# internet_enabled_rov.net
KiCad netlist of a schematic drawn in EAGLE
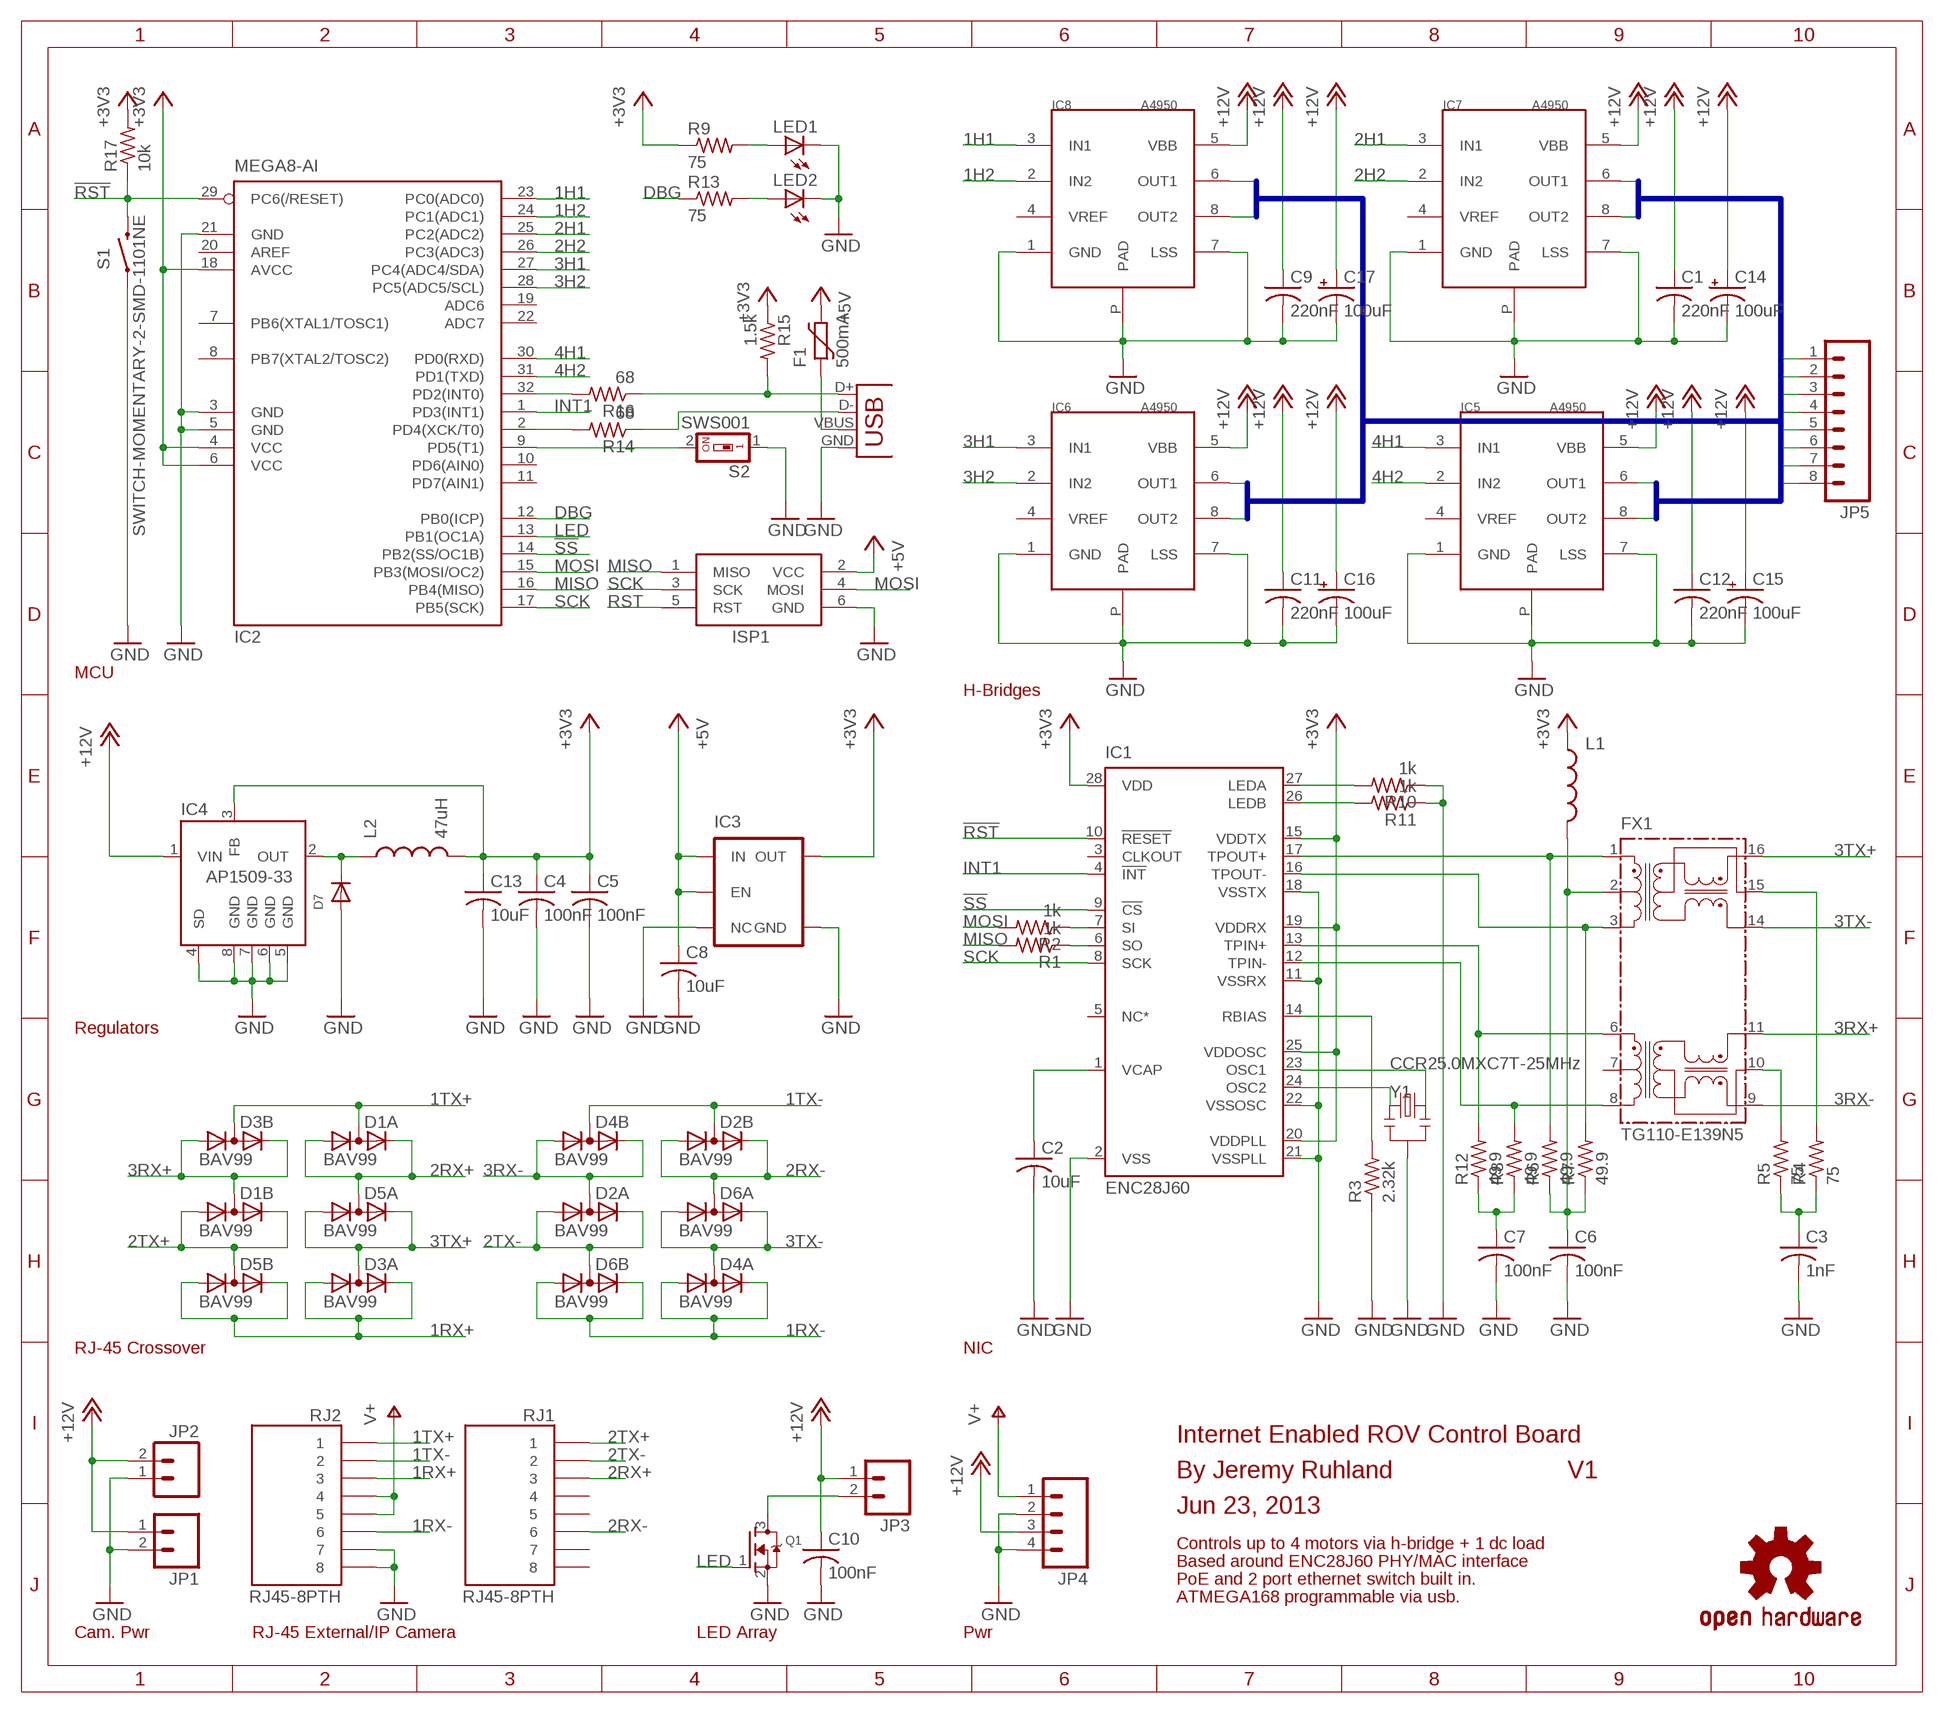
[diagram p0: schematic, sheet 1]

(export (version "E")
  (design (tool "Eeschema 10.0.6"))
  (components
    (comp (ref "C1")
      (value "220nF")
      (footprint "eagle-import:C1206")
      (libsource (lib "eagle-import") (part "C-USC1206"))
    )
    (comp (ref "C2")
      (value "10uF")
      (footprint "eagle-import:C1206")
      (libsource (lib "eagle-import") (part "C-USC1206"))
    )
    (comp (ref "C3")
      (value "1nF")
      (footprint "eagle-import:C1206")
      (libsource (lib "eagle-import") (part "C-USC1206"))
    )
    (comp (ref "C4")
      (value "100nF")
      (footprint "eagle-import:C1206")
      (libsource (lib "eagle-import") (part "C-USC1206"))
    )
    (comp (ref "C5")
      (value "100nF")
      (footprint "eagle-import:C1206")
      (libsource (lib "eagle-import") (part "C-USC1206"))
    )
    (comp (ref "C6")
      (value "100nF")
      (footprint "eagle-import:C1206")
      (libsource (lib "eagle-import") (part "C-USC1206"))
    )
    (comp (ref "C7")
      (value "100nF")
      (footprint "eagle-import:C1206")
      (libsource (lib "eagle-import") (part "C-USC1206"))
    )
    (comp (ref "C8")
      (value "10uF")
      (footprint "eagle-import:C1206")
      (libsource (lib "eagle-import") (part "C-USC1206"))
    )
    (comp (ref "C9")
      (value "220nF")
      (footprint "eagle-import:C1206")
      (libsource (lib "eagle-import") (part "C-USC1206"))
    )
    (comp (ref "C10")
      (value "100nF")
      (footprint "eagle-import:C1206")
      (libsource (lib "eagle-import") (part "C-USC1206"))
    )
    (comp (ref "C11")
      (value "220nF")
      (footprint "eagle-import:C1206")
      (libsource (lib "eagle-import") (part "C-USC1206"))
    )
    (comp (ref "C12")
      (value "220nF")
      (footprint "eagle-import:C1206")
      (libsource (lib "eagle-import") (part "C-USC1206"))
    )
    (comp (ref "C13")
      (value "10uF")
      (footprint "eagle-import:C1206")
      (libsource (lib "eagle-import") (part "C-USC1206"))
    )
    (comp (ref "C14")
      (value "100uF")
      (footprint "eagle-import:PANASONIC_D")
      (libsource (lib "eagle-import") (part "CAP_POLD"))
    )
    (comp (ref "C15")
      (value "100uF")
      (footprint "eagle-import:PANASONIC_D")
      (libsource (lib "eagle-import") (part "CAP_POLD"))
    )
    (comp (ref "C16")
      (value "100uF")
      (footprint "eagle-import:PANASONIC_D")
      (libsource (lib "eagle-import") (part "CAP_POLD"))
    )
    (comp (ref "C17")
      (value "100uF")
      (footprint "eagle-import:PANASONIC_D")
      (libsource (lib "eagle-import") (part "CAP_POLD"))
    )
    (comp (ref "D1")
      (value "BAV99")
      (footprint "eagle-import:SOT363")
      (libsource (lib "eagle-import") (part "BAV99"))
    )
    (comp (ref "D2")
      (value "BAV99")
      (footprint "eagle-import:SOT363")
      (libsource (lib "eagle-import") (part "BAV99"))
    )
    (comp (ref "D3")
      (value "BAV99")
      (footprint "eagle-import:SOT363")
      (libsource (lib "eagle-import") (part "BAV99"))
    )
    (comp (ref "D4")
      (value "BAV99")
      (footprint "eagle-import:SOT363")
      (libsource (lib "eagle-import") (part "BAV99"))
    )
    (comp (ref "D5")
      (value "BAV99")
      (footprint "eagle-import:SOT363")
      (libsource (lib "eagle-import") (part "BAV99"))
    )
    (comp (ref "D6")
      (value "BAV99")
      (footprint "eagle-import:SOT363")
      (libsource (lib "eagle-import") (part "BAV99"))
    )
    (comp (ref "D7")
      (value "DIODESOD-123")
      (footprint "eagle-import:SOD-123")
      (libsource (lib "eagle-import") (part "DIODESOD-123"))
    )
    (comp (ref "F1")
      (value "500mA")
      (footprint "eagle-import:PTC0805")
      (libsource (lib "eagle-import") (part "FUSE_PTC-0805"))
    )
    (comp (ref "FX1")
      (value "TG110-E139N5")
      (footprint "eagle-import:N5")
      (libsource (lib "eagle-import") (part "TG110-EN5139"))
    )
    (comp (ref "IC1")
      (value "ENC28J60")
      (footprint "eagle-import:SO28W")
      (libsource (lib "eagle-import") (part "ENC28J60"))
    )
    (comp (ref "IC2")
      (value "MEGA8-AI")
      (footprint "eagle-import:TQFP32-08")
      (fields (field (name "MPN") "ATMEGA8-16AU"))
      (libsource (lib "eagle-import") (part "MEGA8-AI"))
    )
    (comp (ref "IC3")
      (value "V_REG_TPS76433SOT23-5")
      (footprint "eagle-import:SOT23-5")
      (libsource (lib "eagle-import") (part "V_REG_TPS76433SOT23-5"))
    )
    (comp (ref "IC4")
      (value "AP1509-33")
      (footprint "eagle-import:SOP-8")
      (libsource (lib "eagle-import") (part "AP1509"))
    )
    (comp (ref "IC5")
      (value "A4950")
      (footprint "eagle-import:SOIC-8-PAD")
      (libsource (lib "eagle-import") (part "A4950"))
    )
    (comp (ref "IC6")
      (value "A4950")
      (footprint "eagle-import:SOIC-8-PAD")
      (libsource (lib "eagle-import") (part "A4950"))
    )
    (comp (ref "IC7")
      (value "A4950")
      (footprint "eagle-import:SOIC-8-PAD")
      (libsource (lib "eagle-import") (part "A4950"))
    )
    (comp (ref "IC8")
      (value "A4950")
      (footprint "eagle-import:SOIC-8-PAD")
      (libsource (lib "eagle-import") (part "A4950"))
    )
    (comp (ref "ISP1")
      (value "AVRISP-6")
      (footprint "eagle-import:AVRISP")
      (libsource (lib "eagle-import") (part "AVRISP-6"))
    )
    (comp (ref "JP1")
      (value "M02LOCK")
      (footprint "eagle-import:1X02_LOCK")
      (libsource (lib "eagle-import") (part "M02LOCK"))
    )
    (comp (ref "JP2")
      (value "M02LOCK")
      (footprint "eagle-import:1X02_LOCK")
      (libsource (lib "eagle-import") (part "M02LOCK"))
    )
    (comp (ref "JP3")
      (value "M02LOCK")
      (footprint "eagle-import:1X02_LOCK")
      (libsource (lib "eagle-import") (part "M02LOCK"))
    )
    (comp (ref "JP4")
      (value "M04SCREW_LOCK")
      (footprint "eagle-import:SCREWTERMINAL-3.5MM-4_LOCK")
      (libsource (lib "eagle-import") (part "M04SCREW_LOCK"))
    )
    (comp (ref "JP5")
      (value "M083.5MM-8")
      (footprint "eagle-import:SCREWTERMINAL-3.5MM-8")
      (libsource (lib "eagle-import") (part "M083.5MM-8"))
    )
    (comp (ref "L1")
      (value "INDUCTOR1210")
      (footprint "eagle-import:1210")
      (libsource (lib "eagle-import") (part "INDUCTOR1210"))
    )
    (comp (ref "L2")
      (value "47uH")
      (footprint "eagle-import:1210")
      (libsource (lib "eagle-import") (part "INDUCTOR1210"))
    )
    (comp (ref "LED1")
      (value "LEDCHIPLED_1206")
      (footprint "eagle-import:CHIPLED_1206")
      (libsource (lib "eagle-import") (part "LEDCHIPLED_1206"))
    )
    (comp (ref "LED2")
      (value "LEDCHIPLED_1206")
      (footprint "eagle-import:CHIPLED_1206")
      (libsource (lib "eagle-import") (part "LEDCHIPLED_1206"))
    )
    (comp (ref "Q1")
      (value "MOSFET-NREFLOW")
      (footprint "eagle-import:SOT23")
      (libsource (lib "eagle-import") (part "MOSFET-NREFLOW"))
    )
    (comp (ref "R1")
      (value "1k")
      (footprint "eagle-import:R1206")
      (libsource (lib "eagle-import") (part "R-US_R1206"))
    )
    (comp (ref "R2")
      (value "1k")
      (footprint "eagle-import:R1206")
      (libsource (lib "eagle-import") (part "R-US_R1206"))
    )
    (comp (ref "R3")
      (value "2.32k")
      (footprint "eagle-import:R1206")
      (libsource (lib "eagle-import") (part "R-US_R1206"))
    )
    (comp (ref "R4")
      (value "75")
      (footprint "eagle-import:R1206")
      (libsource (lib "eagle-import") (part "R-US_R1206"))
    )
    (comp (ref "R5")
      (value "75")
      (footprint "eagle-import:R1206")
      (libsource (lib "eagle-import") (part "R-US_R1206"))
    )
    (comp (ref "R6")
      (value "49.9")
      (footprint "eagle-import:R1206")
      (libsource (lib "eagle-import") (part "R-US_R1206"))
    )
    (comp (ref "R7")
      (value "49.9")
      (footprint "eagle-import:R1206")
      (libsource (lib "eagle-import") (part "R-US_R1206"))
    )
    (comp (ref "R8")
      (value "49.9")
      (footprint "eagle-import:R1206")
      (libsource (lib "eagle-import") (part "R-US_R1206"))
    )
    (comp (ref "R9")
      (value "75")
      (footprint "eagle-import:R1206")
      (libsource (lib "eagle-import") (part "R-US_R1206"))
    )
    (comp (ref "R10")
      (value "1k")
      (footprint "eagle-import:R1206")
      (libsource (lib "eagle-import") (part "R-US_R1206"))
    )
    (comp (ref "R11")
      (value "1k")
      (footprint "eagle-import:R1206")
      (libsource (lib "eagle-import") (part "R-US_R1206"))
    )
    (comp (ref "R12")
      (value "49.9")
      (footprint "eagle-import:R1206")
      (libsource (lib "eagle-import") (part "R-US_R1206"))
    )
    (comp (ref "R13")
      (value "75")
      (footprint "eagle-import:R1206")
      (libsource (lib "eagle-import") (part "R-US_R1206"))
    )
    (comp (ref "R14")
      (value "68")
      (footprint "eagle-import:R1206")
      (libsource (lib "eagle-import") (part "R-US_R1206"))
    )
    (comp (ref "R15")
      (value "1.5k")
      (footprint "eagle-import:R1206")
      (libsource (lib "eagle-import") (part "R-US_R1206"))
    )
    (comp (ref "R16")
      (value "68")
      (footprint "eagle-import:R1206")
      (libsource (lib "eagle-import") (part "R-US_R1206"))
    )
    (comp (ref "R17")
      (value "10k")
      (footprint "eagle-import:R1206")
      (libsource (lib "eagle-import") (part "R-US_R1206"))
    )
    (comp (ref "RJ1")
      (value "RJ45-8PTH")
      (footprint "eagle-import:RJ45-8")
      (libsource (lib "eagle-import") (part "RJ45-8PTH"))
    )
    (comp (ref "RJ2")
      (value "RJ45-8PTH")
      (footprint "eagle-import:RJ45-8")
      (libsource (lib "eagle-import") (part "RJ45-8PTH"))
    )
    (comp (ref "S1")
      (value "SWITCH-MOMENTARY-2-SMD-1101NE")
      (footprint "eagle-import:TACTILE-SWITCH-1101NE")
      (libsource (lib "eagle-import") (part "SWITCH-MOMENTARY-2-SMD-1101NE"))
    )
    (comp (ref "S2")
      (value "SWS001")
      (footprint "eagle-import:SMS-001")
      (libsource (lib "eagle-import") (part "SWS001"))
    )
    (comp (ref "U$1")
      (value "OSHW-LOGOL")
      (footprint "eagle-import:OSHW-LOGO-L")
      (libsource (lib "eagle-import") (part "OSHW-LOGOL"))
    )
    (comp (ref "X1")
      (value "USBSMD")
      (footprint "eagle-import:USB-MINIB")
      (libsource (lib "eagle-import") (part "USBSMD"))
    )
    (comp (ref "Y1")
      (value "CCR25.0MXC7T-25MHz")
      (footprint "eagle-import:RESONATOR-SMD")
      (libsource (lib "eagle-import") (part "RESONATORSMD"))
    )
  )
  (nets
    (net (code "1") (name "+3V3") (class "Default")
      (node (ref "C13") (pin "1") (pinfunction "1_1") (pintype "passive"))
      (node (ref "C4") (pin "1") (pinfunction "1_1") (pintype "passive"))
      (node (ref "C5") (pin "1") (pinfunction "1_1") (pintype "passive"))
      (node (ref "IC1") (pin "15") (pinfunction "VDDTX_15") (pintype "input"))
      (node (ref "IC1") (pin "19") (pinfunction "VDDRX_19") (pintype "input"))
      (node (ref "IC1") (pin "20") (pinfunction "VDDPLL_20") (pintype "input"))
      (node (ref "IC1") (pin "25") (pinfunction "VDDOSC_25") (pintype "input"))
      (node (ref "IC1") (pin "28") (pinfunction "VDD_28") (pintype "input"))
      (node (ref "IC2") (pin "18") (pinfunction "AVCC_18") (pintype "power_in"))
      (node (ref "IC2") (pin "4") (pinfunction "VCC_4") (pintype "power_in"))
      (node (ref "IC2") (pin "6") (pinfunction "VCC_6") (pintype "power_in"))
      (node (ref "IC3") (pin "5") (pinfunction "OUT_5") (pintype "passive"))
      (node (ref "IC4") (pin "3") (pinfunction "FB_3") (pintype "bidirectional"))
      (node (ref "L1") (pin "1") (pinfunction "1_1") (pintype "passive"))
      (node (ref "L2") (pin "2") (pinfunction "2_2") (pintype "passive"))
      (node (ref "R15") (pin "1") (pinfunction "1_1") (pintype "passive"))
      (node (ref "R17") (pin "2") (pinfunction "2_2") (pintype "passive"))
      (node (ref "R9") (pin "1") (pinfunction "1_1") (pintype "passive"))
    )
    (net (code "2") (name "+5V") (class "Default")
      (node (ref "C8") (pin "1") (pinfunction "1_1") (pintype "passive"))
      (node (ref "F1") (pin "2") (pinfunction "2_2") (pintype "passive"))
      (node (ref "IC3") (pin "1") (pinfunction "IN_1") (pintype "input"))
      (node (ref "IC3") (pin "3") (pinfunction "EN_3") (pintype "input"))
      (node (ref "ISP1") (pin "2") (pinfunction "VCC_2") (pintype "power_in"))
    )
    (net (code "3") (name "+12V") (class "Default")
      (node (ref "C1") (pin "1") (pinfunction "1_1") (pintype "passive"))
      (node (ref "C10") (pin "1") (pinfunction "1_1") (pintype "passive"))
      (node (ref "C11") (pin "1") (pinfunction "1_1") (pintype "passive"))
      (node (ref "C12") (pin "1") (pinfunction "1_1") (pintype "passive"))
      (node (ref "C14") (pin "+") (pinfunction "+_+") (pintype "passive"))
      (node (ref "C15") (pin "+") (pinfunction "+_+") (pintype "passive"))
      (node (ref "C16") (pin "+") (pinfunction "+_+") (pintype "passive"))
      (node (ref "C17") (pin "+") (pinfunction "+_+") (pintype "passive"))
      (node (ref "C9") (pin "1") (pinfunction "1_1") (pintype "passive"))
      (node (ref "IC4") (pin "1") (pinfunction "VIN_1") (pintype "bidirectional"))
      (node (ref "IC5") (pin "5") (pinfunction "VBB_5") (pintype "bidirectional"))
      (node (ref "IC6") (pin "5") (pinfunction "VBB_5") (pintype "bidirectional"))
      (node (ref "IC7") (pin "5") (pinfunction "VBB_5") (pintype "bidirectional"))
      (node (ref "IC8") (pin "5") (pinfunction "VBB_5") (pintype "bidirectional"))
      (node (ref "JP1") (pin "1") (pinfunction "1_1") (pintype "passive"))
      (node (ref "JP2") (pin "2") (pinfunction "2_2") (pintype "passive"))
      (node (ref "JP3") (pin "1") (pinfunction "1_1") (pintype "passive"))
      (node (ref "JP4") (pin "3") (pinfunction "3_3") (pintype "passive"))
    )
    (net (code "4") (name "/1H1") (class "Default")
      (node (ref "IC2") (pin "23") (pinfunction "PC0(ADC0)_23") (pintype "bidirectional"))
      (node (ref "IC8") (pin "3") (pinfunction "IN1_3") (pintype "bidirectional"))
    )
    (net (code "5") (name "/1H2") (class "Default")
      (node (ref "IC2") (pin "24") (pinfunction "PC1(ADC1)_24") (pintype "bidirectional"))
      (node (ref "IC8") (pin "2") (pinfunction "IN2_2") (pintype "bidirectional"))
    )
    (net (code "6") (name "/1RX+") (class "Default")
      (node (ref "D3") (pin "1") (pinfunction "A_1") (pintype "passive"))
      (node (ref "D3") (pin "2") (pinfunction "K_2") (pintype "passive"))
      (node (ref "D5") (pin "4") (pinfunction "A_4") (pintype "passive"))
      (node (ref "D5") (pin "5") (pinfunction "K_5") (pintype "passive"))
      (node (ref "RJ2") (pin "3") (pinfunction "3_3") (pintype "bidirectional"))
    )
    (net (code "7") (name "/1RX-") (class "Default")
      (node (ref "D4") (pin "1") (pinfunction "A_1") (pintype "passive"))
      (node (ref "D4") (pin "2") (pinfunction "K_2") (pintype "passive"))
      (node (ref "D6") (pin "4") (pinfunction "A_4") (pintype "passive"))
      (node (ref "D6") (pin "5") (pinfunction "K_5") (pintype "passive"))
      (node (ref "RJ2") (pin "6") (pinfunction "6_6") (pintype "bidirectional"))
    )
    (net (code "8") (name "/1TX+") (class "Default")
      (node (ref "D1") (pin "6") (pinfunction "AK_6") (pintype "passive"))
      (node (ref "D3") (pin "3") (pinfunction "AK_3") (pintype "passive"))
      (node (ref "RJ2") (pin "1") (pinfunction "1_1") (pintype "bidirectional"))
    )
    (net (code "9") (name "/1TX-") (class "Default")
      (node (ref "D2") (pin "3") (pinfunction "AK_3") (pintype "passive"))
      (node (ref "D4") (pin "3") (pinfunction "AK_3") (pintype "passive"))
      (node (ref "RJ2") (pin "2") (pinfunction "2_2") (pintype "bidirectional"))
    )
    (net (code "10") (name "/2H1") (class "Default")
      (node (ref "IC2") (pin "25") (pinfunction "PC2(ADC2)_25") (pintype "bidirectional"))
      (node (ref "IC7") (pin "3") (pinfunction "IN1_3") (pintype "bidirectional"))
    )
    (net (code "11") (name "/2H2") (class "Default")
      (node (ref "IC2") (pin "26") (pinfunction "PC3(ADC3)_26") (pintype "bidirectional"))
      (node (ref "IC7") (pin "2") (pinfunction "IN2_2") (pintype "bidirectional"))
    )
    (net (code "12") (name "/2RX+") (class "Default")
      (node (ref "D1") (pin "1") (pinfunction "A_1") (pintype "passive"))
      (node (ref "D1") (pin "2") (pinfunction "K_2") (pintype "passive"))
      (node (ref "D5") (pin "6") (pinfunction "AK_6") (pintype "passive"))
      (node (ref "RJ1") (pin "3") (pinfunction "3_3") (pintype "bidirectional"))
    )
    (net (code "13") (name "/2RX-") (class "Default")
      (node (ref "D2") (pin "4") (pinfunction "A_4") (pintype "passive"))
      (node (ref "D2") (pin "5") (pinfunction "K_5") (pintype "passive"))
      (node (ref "D6") (pin "6") (pinfunction "AK_6") (pintype "passive"))
      (node (ref "RJ1") (pin "6") (pinfunction "6_6") (pintype "bidirectional"))
    )
    (net (code "14") (name "/2TX+") (class "Default")
      (node (ref "D1") (pin "4") (pinfunction "A_4") (pintype "passive"))
      (node (ref "D1") (pin "5") (pinfunction "K_5") (pintype "passive"))
      (node (ref "D5") (pin "3") (pinfunction "AK_3") (pintype "passive"))
      (node (ref "RJ1") (pin "1") (pinfunction "1_1") (pintype "bidirectional"))
    )
    (net (code "15") (name "/2TX-") (class "Default")
      (node (ref "D2") (pin "1") (pinfunction "A_1") (pintype "passive"))
      (node (ref "D2") (pin "2") (pinfunction "K_2") (pintype "passive"))
      (node (ref "D6") (pin "3") (pinfunction "AK_3") (pintype "passive"))
      (node (ref "RJ1") (pin "2") (pinfunction "2_2") (pintype "bidirectional"))
    )
    (net (code "16") (name "/3H1") (class "Default")
      (node (ref "IC2") (pin "27") (pinfunction "PC4(ADC4/SDA)_27") (pintype "bidirectional"))
      (node (ref "IC6") (pin "3") (pinfunction "IN1_3") (pintype "bidirectional"))
    )
    (net (code "17") (name "/3H2") (class "Default")
      (node (ref "IC2") (pin "28") (pinfunction "PC5(ADC5/SCL)_28") (pintype "bidirectional"))
      (node (ref "IC6") (pin "2") (pinfunction "IN2_2") (pintype "bidirectional"))
    )
    (net (code "18") (name "/3RX+") (class "Default")
      (node (ref "D1") (pin "3") (pinfunction "AK_3") (pintype "passive"))
      (node (ref "D3") (pin "4") (pinfunction "A_4") (pintype "passive"))
      (node (ref "D3") (pin "5") (pinfunction "K_5") (pintype "passive"))
      (node (ref "FX1") (pin "11") (pinfunction "11_11") (pintype "passive"))
    )
    (net (code "19") (name "/3RX-") (class "Default")
      (node (ref "D2") (pin "6") (pinfunction "AK_6") (pintype "passive"))
      (node (ref "D4") (pin "4") (pinfunction "A_4") (pintype "passive"))
      (node (ref "D4") (pin "5") (pinfunction "K_5") (pintype "passive"))
      (node (ref "FX1") (pin "9") (pinfunction "9_9") (pintype "passive"))
    )
    (net (code "20") (name "/3TX+") (class "Default")
      (node (ref "D3") (pin "6") (pinfunction "AK_6") (pintype "passive"))
      (node (ref "D5") (pin "1") (pinfunction "A_1") (pintype "passive"))
      (node (ref "D5") (pin "2") (pinfunction "K_2") (pintype "passive"))
      (node (ref "FX1") (pin "16") (pinfunction "16_16") (pintype "passive"))
    )
    (net (code "21") (name "/3TX-") (class "Default")
      (node (ref "D4") (pin "6") (pinfunction "AK_6") (pintype "passive"))
      (node (ref "D6") (pin "1") (pinfunction "A_1") (pintype "passive"))
      (node (ref "D6") (pin "2") (pinfunction "K_2") (pintype "passive"))
      (node (ref "FX1") (pin "14") (pinfunction "14_14") (pintype "passive"))
    )
    (net (code "22") (name "/4H1") (class "Default")
      (node (ref "IC2") (pin "30") (pinfunction "PD0(RXD)_30") (pintype "bidirectional"))
      (node (ref "IC5") (pin "3") (pinfunction "IN1_3") (pintype "bidirectional"))
    )
    (net (code "23") (name "/4H2") (class "Default")
      (node (ref "IC2") (pin "31") (pinfunction "PD1(TXD)_31") (pintype "bidirectional"))
      (node (ref "IC5") (pin "2") (pinfunction "IN2_2") (pintype "bidirectional"))
    )
    (net (code "24") (name "/DBG") (class "Default")
      (node (ref "IC2") (pin "12") (pinfunction "PB0(ICP)_12") (pintype "bidirectional"))
      (node (ref "R13") (pin "1") (pinfunction "1_1") (pintype "passive"))
    )
    (net (code "25") (name "/INT1") (class "Default")
      (node (ref "IC1") (pin "4") (pinfunction "~{INT}_4") (pintype "output"))
      (node (ref "IC2") (pin "1") (pinfunction "PD3(INT1)_1") (pintype "bidirectional"))
    )
    (net (code "26") (name "/LED") (class "Default")
      (node (ref "IC2") (pin "13") (pinfunction "PB1(OC1A)_13") (pintype "bidirectional"))
      (node (ref "Q1") (pin "1") (pinfunction "G_1") (pintype "bidirectional"))
    )
    (net (code "27") (name "/MISO") (class "Default")
      (node (ref "IC2") (pin "16") (pinfunction "PB4(MISO)_16") (pintype "bidirectional"))
      (node (ref "ISP1") (pin "1") (pinfunction "MISO_1") (pintype "input"))
      (node (ref "R1") (pin "2") (pinfunction "2_2") (pintype "passive"))
    )
    (net (code "28") (name "/MOSI") (class "Default")
      (node (ref "IC2") (pin "15") (pinfunction "PB3(MOSI/OC2)_15") (pintype "bidirectional"))
      (node (ref "ISP1") (pin "4") (pinfunction "MOSI_4") (pintype "output"))
      (node (ref "R2") (pin "2") (pinfunction "2_2") (pintype "passive"))
    )
    (net (code "29") (name "/OUT1") (class "Default")
      (node (ref "IC8") (pin "8") (pinfunction "OUT2_8") (pintype "bidirectional"))
      (node (ref "JP5") (pin "2") (pinfunction "2_2") (pintype "passive"))
    )
    (net (code "30") (name "/OUT2") (class "Default")
      (node (ref "IC8") (pin "6") (pinfunction "OUT1_6") (pintype "bidirectional"))
      (node (ref "JP5") (pin "1") (pinfunction "1_1") (pintype "passive"))
    )
    (net (code "31") (name "/OUT3") (class "Default")
      (node (ref "IC7") (pin "8") (pinfunction "OUT2_8") (pintype "bidirectional"))
      (node (ref "JP5") (pin "4") (pinfunction "4_4") (pintype "passive"))
    )
    (net (code "32") (name "/OUT4") (class "Default")
      (node (ref "IC7") (pin "6") (pinfunction "OUT1_6") (pintype "bidirectional"))
      (node (ref "JP5") (pin "3") (pinfunction "3_3") (pintype "passive"))
    )
    (net (code "33") (name "/OUT5") (class "Default")
      (node (ref "IC6") (pin "8") (pinfunction "OUT2_8") (pintype "bidirectional"))
      (node (ref "JP5") (pin "6") (pinfunction "6_6") (pintype "passive"))
    )
    (net (code "34") (name "/OUT6") (class "Default")
      (node (ref "IC6") (pin "6") (pinfunction "OUT1_6") (pintype "bidirectional"))
      (node (ref "JP5") (pin "5") (pinfunction "5_5") (pintype "passive"))
    )
    (net (code "35") (name "/OUT7") (class "Default")
      (node (ref "IC5") (pin "8") (pinfunction "OUT2_8") (pintype "bidirectional"))
      (node (ref "JP5") (pin "8") (pinfunction "8_8") (pintype "passive"))
    )
    (net (code "36") (name "/OUT8") (class "Default")
      (node (ref "IC5") (pin "6") (pinfunction "OUT1_6") (pintype "bidirectional"))
      (node (ref "JP5") (pin "7") (pinfunction "7_7") (pintype "passive"))
    )
    (net (code "37") (name "/RST") (class "Default")
      (node (ref "ISP1") (pin "5") (pinfunction "RST_5") (pintype "output"))
    )
    (net (code "38") (name "/SCK") (class "Default")
      (node (ref "IC1") (pin "8") (pinfunction "SCK_8") (pintype "input"))
      (node (ref "IC2") (pin "17") (pinfunction "PB5(SCK)_17") (pintype "bidirectional"))
      (node (ref "ISP1") (pin "3") (pinfunction "SCK_3") (pintype "output"))
    )
    (net (code "39") (name "/~{RST}") (class "Default")
      (node (ref "IC1") (pin "10") (pinfunction "~{RESET}_10") (pintype "input"))
      (node (ref "IC2") (pin "29") (pinfunction "PC6(/RESET)_29") (pintype "bidirectional"))
      (node (ref "R17") (pin "1") (pinfunction "1_1") (pintype "passive"))
      (node (ref "S1") (pin "P$2") (pinfunction "2_P$2") (pintype "passive"))
    )
    (net (code "40") (name "/~{SS}") (class "Default")
      (node (ref "IC1") (pin "9") (pinfunction "~{CS}_9") (pintype "input"))
      (node (ref "IC2") (pin "14") (pinfunction "PB2(SS/OC1B)_14") (pintype "bidirectional"))
    )
    (net (code "41") (name "GND") (class "Default")
      (node (ref "C1") (pin "2") (pinfunction "2_2") (pintype "passive"))
      (node (ref "C10") (pin "2") (pinfunction "2_2") (pintype "passive"))
      (node (ref "C11") (pin "2") (pinfunction "2_2") (pintype "passive"))
      (node (ref "C12") (pin "2") (pinfunction "2_2") (pintype "passive"))
      (node (ref "C13") (pin "2") (pinfunction "2_2") (pintype "passive"))
      (node (ref "C14") (pin "-") (pinfunction "-_-") (pintype "passive"))
      (node (ref "C15") (pin "-") (pinfunction "-_-") (pintype "passive"))
      (node (ref "C16") (pin "-") (pinfunction "-_-") (pintype "passive"))
      (node (ref "C17") (pin "-") (pinfunction "-_-") (pintype "passive"))
      (node (ref "C2") (pin "2") (pinfunction "2_2") (pintype "passive"))
      (node (ref "C3") (pin "2") (pinfunction "2_2") (pintype "passive"))
      (node (ref "C4") (pin "2") (pinfunction "2_2") (pintype "passive"))
      (node (ref "C5") (pin "2") (pinfunction "2_2") (pintype "passive"))
      (node (ref "C6") (pin "2") (pinfunction "2_2") (pintype "passive"))
      (node (ref "C7") (pin "2") (pinfunction "2_2") (pintype "passive"))
      (node (ref "C8") (pin "2") (pinfunction "2_2") (pintype "passive"))
      (node (ref "C9") (pin "2") (pinfunction "2_2") (pintype "passive"))
      (node (ref "D7") (pin "A") (pinfunction "A_A") (pintype "passive"))
      (node (ref "IC1") (pin "11") (pinfunction "VSSRX_11") (pintype "input"))
      (node (ref "IC1") (pin "18") (pinfunction "VSSTX_18") (pintype "input"))
      (node (ref "IC1") (pin "2") (pinfunction "VSS_2") (pintype "input"))
      (node (ref "IC1") (pin "21") (pinfunction "VSSPLL_21") (pintype "input"))
      (node (ref "IC1") (pin "22") (pinfunction "VSSOSC_22") (pintype "input"))
      (node (ref "IC2") (pin "21") (pinfunction "GND_21") (pintype "power_in"))
      (node (ref "IC2") (pin "3") (pinfunction "GND_3") (pintype "power_in"))
      (node (ref "IC2") (pin "5") (pinfunction "GND_5") (pintype "power_in"))
      (node (ref "IC3") (pin "2") (pinfunction "GND_2") (pintype "input"))
      (node (ref "IC3") (pin "4") (pinfunction "NC_4") (pintype "input"))
      (node (ref "IC4") (pin "4") (pinfunction "SD_4") (pintype "bidirectional"))
      (node (ref "IC4") (pin "5") (pinfunction "GND_5") (pintype "bidirectional"))
      (node (ref "IC4") (pin "6") (pinfunction "GND_6") (pintype "bidirectional"))
      (node (ref "IC4") (pin "7") (pinfunction "GND_7") (pintype "bidirectional"))
      (node (ref "IC4") (pin "8") (pinfunction "GND_8") (pintype "bidirectional"))
      (node (ref "IC5") (pin "1") (pinfunction "GND_1") (pintype "bidirectional"))
      (node (ref "IC5") (pin "7") (pinfunction "LSS_7") (pintype "bidirectional"))
      (node (ref "IC5") (pin "P") (pinfunction "PAD_P") (pintype "bidirectional"))
      (node (ref "IC6") (pin "1") (pinfunction "GND_1") (pintype "bidirectional"))
      (node (ref "IC6") (pin "7") (pinfunction "LSS_7") (pintype "bidirectional"))
      (node (ref "IC6") (pin "P") (pinfunction "PAD_P") (pintype "bidirectional"))
      (node (ref "IC7") (pin "1") (pinfunction "GND_1") (pintype "bidirectional"))
      (node (ref "IC7") (pin "7") (pinfunction "LSS_7") (pintype "bidirectional"))
      (node (ref "IC7") (pin "P") (pinfunction "PAD_P") (pintype "bidirectional"))
      (node (ref "IC8") (pin "1") (pinfunction "GND_1") (pintype "bidirectional"))
      (node (ref "IC8") (pin "7") (pinfunction "LSS_7") (pintype "bidirectional"))
      (node (ref "IC8") (pin "P") (pinfunction "PAD_P") (pintype "bidirectional"))
      (node (ref "ISP1") (pin "6") (pinfunction "GND_6") (pintype "power_in"))
      (node (ref "JP1") (pin "2") (pinfunction "2_2") (pintype "passive"))
      (node (ref "JP2") (pin "1") (pinfunction "1_1") (pintype "passive"))
      (node (ref "JP4") (pin "2") (pinfunction "2_2") (pintype "passive"))
      (node (ref "JP4") (pin "4") (pinfunction "4_4") (pintype "passive"))
      (node (ref "LED1") (pin "C") (pinfunction "C_C") (pintype "passive"))
      (node (ref "LED2") (pin "C") (pinfunction "C_C") (pintype "passive"))
      (node (ref "Q1") (pin "2") (pinfunction "S_2") (pintype "bidirectional"))
      (node (ref "R10") (pin "1") (pinfunction "1_1") (pintype "passive"))
      (node (ref "R11") (pin "1") (pinfunction "1_1") (pintype "passive"))
      (node (ref "R3") (pin "1") (pinfunction "1_1") (pintype "passive"))
      (node (ref "RJ2") (pin "7") (pinfunction "7_7") (pintype "bidirectional"))
      (node (ref "RJ2") (pin "8") (pinfunction "8_8") (pintype "bidirectional"))
      (node (ref "S1") (pin "P$1") (pinfunction "1_P$1") (pintype "passive"))
      (node (ref "S2") (pin "1") (pinfunction "1_1") (pintype "passive"))
      (node (ref "X1") (pin "GND") (pinfunction "GND_GND") (pintype "bidirectional"))
      (node (ref "Y1") (pin "2") (pinfunction "2_2") (pintype "passive"))
    )
    (net (code "42") (name "Net-(C3-Pad1)") (class "Default")
      (node (ref "C3") (pin "1") (pinfunction "1_1") (pintype "passive"))
      (node (ref "R4") (pin "1") (pinfunction "1_1") (pintype "passive"))
      (node (ref "R5") (pin "1") (pinfunction "1_1") (pintype "passive"))
    )
    (net (code "43") (name "Net-(C6-Pad1)") (class "Default")
      (node (ref "C6") (pin "1") (pinfunction "1_1") (pintype "passive"))
      (node (ref "FX1") (pin "2") (pinfunction "2_2") (pintype "passive"))
      (node (ref "L1") (pin "2") (pinfunction "2_2") (pintype "passive"))
      (node (ref "R6") (pin "1") (pinfunction "1_1") (pintype "passive"))
      (node (ref "R7") (pin "1") (pinfunction "1_1") (pintype "passive"))
    )
    (net (code "44") (name "Net-(C7-Pad1)") (class "Default")
      (node (ref "C7") (pin "1") (pinfunction "1_1") (pintype "passive"))
      (node (ref "R12") (pin "1") (pinfunction "1_1") (pintype "passive"))
      (node (ref "R8") (pin "1") (pinfunction "1_1") (pintype "passive"))
    )
    (net (code "45") (name "Net-(F1-Pad1)") (class "Default")
      (node (ref "F1") (pin "1") (pinfunction "1_1") (pintype "passive"))
      (node (ref "X1") (pin "VBUS") (pinfunction "VBUS_VBUS") (pintype "bidirectional"))
    )
    (net (code "46") (name "Net-(FX1-Pad10)") (class "Default")
      (node (ref "FX1") (pin "10") (pinfunction "10_10") (pintype "passive"))
      (node (ref "R5") (pin "2") (pinfunction "2_2") (pintype "passive"))
    )
    (net (code "47") (name "Net-(FX1-Pad15)") (class "Default")
      (node (ref "FX1") (pin "15") (pinfunction "15_15") (pintype "passive"))
      (node (ref "R4") (pin "2") (pinfunction "2_2") (pintype "passive"))
    )
    (net (code "48") (name "Net-(IC1-LEDA)") (class "Default")
      (node (ref "IC1") (pin "27") (pinfunction "LEDA_27") (pintype "output"))
      (node (ref "R10") (pin "2") (pinfunction "2_2") (pintype "passive"))
    )
    (net (code "49") (name "Net-(IC1-LEDB)") (class "Default")
      (node (ref "IC1") (pin "26") (pinfunction "LEDB_26") (pintype "output"))
      (node (ref "R11") (pin "2") (pinfunction "2_2") (pintype "passive"))
    )
    (net (code "50") (name "Net-(IC1-OSC1)") (class "Default")
      (node (ref "IC1") (pin "23") (pinfunction "OSC1_23") (pintype "input"))
      (node (ref "Y1") (pin "3") (pinfunction "3_3") (pintype "passive"))
    )
    (net (code "51") (name "Net-(IC1-OSC2)") (class "Default")
      (node (ref "IC1") (pin "24") (pinfunction "OSC2_24") (pintype "output"))
      (node (ref "Y1") (pin "1") (pinfunction "1_1") (pintype "passive"))
    )
    (net (code "52") (name "Net-(IC1-RBIAS)") (class "Default")
      (node (ref "IC1") (pin "14") (pinfunction "RBIAS_14") (pintype "input"))
      (node (ref "R3") (pin "2") (pinfunction "2_2") (pintype "passive"))
    )
    (net (code "53") (name "Net-(IC1-SI)") (class "Default")
      (node (ref "IC1") (pin "7") (pinfunction "SI_7") (pintype "input"))
      (node (ref "R2") (pin "1") (pinfunction "1_1") (pintype "passive"))
    )
    (net (code "54") (name "Net-(IC1-SO)") (class "Default")
      (node (ref "IC1") (pin "6") (pinfunction "SO_6") (pintype "output"))
      (node (ref "R1") (pin "1") (pinfunction "1_1") (pintype "passive"))
    )
    (net (code "55") (name "Net-(IC1-TPIN+)") (class "Default")
      (node (ref "FX1") (pin "6") (pinfunction "6_6") (pintype "passive"))
      (node (ref "IC1") (pin "13") (pinfunction "TPIN+_13") (pintype "input"))
      (node (ref "R12") (pin "2") (pinfunction "2_2") (pintype "passive"))
    )
    (net (code "56") (name "Net-(IC1-TPIN-)") (class "Default")
      (node (ref "FX1") (pin "8") (pinfunction "8_8") (pintype "passive"))
      (node (ref "IC1") (pin "12") (pinfunction "TPIN-_12") (pintype "input"))
      (node (ref "R8") (pin "2") (pinfunction "2_2") (pintype "passive"))
    )
    (net (code "57") (name "Net-(IC1-TPOUT+)") (class "Default")
      (node (ref "FX1") (pin "1") (pinfunction "1_1") (pintype "passive"))
      (node (ref "IC1") (pin "17") (pinfunction "TPOUT+_17") (pintype "output"))
      (node (ref "R6") (pin "2") (pinfunction "2_2") (pintype "passive"))
    )
    (net (code "58") (name "Net-(IC1-TPOUT-)") (class "Default")
      (node (ref "FX1") (pin "3") (pinfunction "3_3") (pintype "passive"))
      (node (ref "IC1") (pin "16") (pinfunction "TPOUT-_16") (pintype "output"))
      (node (ref "R7") (pin "2") (pinfunction "2_2") (pintype "passive"))
    )
    (net (code "59") (name "Net-(IC1-VCAP)") (class "Default")
      (node (ref "C2") (pin "1") (pinfunction "1_1") (pintype "passive"))
      (node (ref "IC1") (pin "1") (pinfunction "VCAP_1") (pintype "input"))
    )
    (net (code "60") (name "Net-(IC2-PD2(INT0))") (class "Default")
      (node (ref "IC2") (pin "32") (pinfunction "PD2(INT0)_32") (pintype "bidirectional"))
      (node (ref "R16") (pin "2") (pinfunction "2_2") (pintype "passive"))
    )
    (net (code "61") (name "Net-(IC2-PD4(XCK{slash}T0))") (class "Default")
      (node (ref "IC2") (pin "2") (pinfunction "PD4(XCK/T0)_2") (pintype "bidirectional"))
      (node (ref "R14") (pin "2") (pinfunction "2_2") (pintype "passive"))
    )
    (net (code "62") (name "Net-(IC2-PD5(T1))") (class "Default")
      (node (ref "IC2") (pin "9") (pinfunction "PD5(T1)_9") (pintype "bidirectional"))
      (node (ref "S2") (pin "2") (pinfunction "2_2") (pintype "passive"))
    )
    (net (code "63") (name "Net-(IC4-OUT)") (class "Default")
      (node (ref "D7") (pin "C") (pinfunction "C_C") (pintype "passive"))
      (node (ref "IC4") (pin "2") (pinfunction "OUT_2") (pintype "bidirectional"))
      (node (ref "L2") (pin "1") (pinfunction "1_1") (pintype "passive"))
    )
    (net (code "64") (name "Net-(LED1-PadA)") (class "Default")
      (node (ref "LED1") (pin "A") (pinfunction "A_A") (pintype "passive"))
      (node (ref "R9") (pin "2") (pinfunction "2_2") (pintype "passive"))
    )
    (net (code "65") (name "Net-(LED2-PadA)") (class "Default")
      (node (ref "LED2") (pin "A") (pinfunction "A_A") (pintype "passive"))
      (node (ref "R13") (pin "2") (pinfunction "2_2") (pintype "passive"))
    )
    (net (code "66") (name "Net-(Q1-D)") (class "Default")
      (node (ref "JP3") (pin "2") (pinfunction "2_2") (pintype "passive"))
      (node (ref "Q1") (pin "3") (pinfunction "D_3") (pintype "bidirectional"))
    )
    (net (code "67") (name "Net-(R14-Pad1)") (class "Default")
      (node (ref "R14") (pin "1") (pinfunction "1_1") (pintype "passive"))
      (node (ref "X1") (pin "D-") (pinfunction "D-_D-") (pintype "bidirectional"))
    )
    (net (code "68") (name "Net-(R15-Pad2)") (class "Default")
      (node (ref "R15") (pin "2") (pinfunction "2_2") (pintype "passive"))
      (node (ref "R16") (pin "1") (pinfunction "1_1") (pintype "passive"))
      (node (ref "X1") (pin "D+") (pinfunction "D+_D+") (pintype "bidirectional"))
    )
    (net (code "69") (name "V+") (class "Default")
      (node (ref "JP4") (pin "1") (pinfunction "1_1") (pintype "passive"))
      (node (ref "RJ2") (pin "4") (pinfunction "4_4") (pintype "bidirectional"))
      (node (ref "RJ2") (pin "5") (pinfunction "5_5") (pintype "bidirectional"))
    )
    (net (code "70") (name "unconnected-(FX1-Pad7)") (class "Default")
      (node (ref "FX1") (pin "7") (pinfunction "7_7") (pintype "passive"))
    )
    (net (code "71") (name "unconnected-(IC1-CLKOUT-Pad3)") (class "Default")
      (node (ref "IC1") (pin "3") (pinfunction "CLKOUT_3") (pintype "output"))
    )
    (net (code "72") (name "unconnected-(IC1-NC*-Pad5)") (class "Default")
      (node (ref "IC1") (pin "5") (pinfunction "NC*_5") (pintype "output"))
    )
    (net (code "73") (name "unconnected-(IC2-ADC6-Pad19)") (class "Default")
      (node (ref "IC2") (pin "19") (pinfunction "ADC6_19") (pintype "bidirectional"))
    )
    (net (code "74") (name "unconnected-(IC2-ADC7-Pad22)") (class "Default")
      (node (ref "IC2") (pin "22") (pinfunction "ADC7_22") (pintype "bidirectional"))
    )
    (net (code "75") (name "unconnected-(IC2-AREF-Pad20)") (class "Default")
      (node (ref "IC2") (pin "20") (pinfunction "AREF_20") (pintype "passive"))
    )
    (net (code "76") (name "unconnected-(IC2-PB6(XTAL1{slash}TOSC1)-Pad7)") (class "Default")
      (node (ref "IC2") (pin "7") (pinfunction "PB6(XTAL1/TOSC1)_7") (pintype "bidirectional"))
    )
    (net (code "77") (name "unconnected-(IC2-PB7(XTAL2{slash}TOSC2)-Pad8)") (class "Default")
      (node (ref "IC2") (pin "8") (pinfunction "PB7(XTAL2/TOSC2)_8") (pintype "bidirectional"))
    )
    (net (code "78") (name "unconnected-(IC2-PD6(AIN0)-Pad10)") (class "Default")
      (node (ref "IC2") (pin "10") (pinfunction "PD6(AIN0)_10") (pintype "bidirectional"))
    )
    (net (code "79") (name "unconnected-(IC2-PD7(AIN1)-Pad11)") (class "Default")
      (node (ref "IC2") (pin "11") (pinfunction "PD7(AIN1)_11") (pintype "bidirectional"))
    )
    (net (code "80") (name "unconnected-(IC5-VREF-Pad4)") (class "Default")
      (node (ref "IC5") (pin "4") (pinfunction "VREF_4") (pintype "bidirectional"))
    )
    (net (code "81") (name "unconnected-(IC6-VREF-Pad4)") (class "Default")
      (node (ref "IC6") (pin "4") (pinfunction "VREF_4") (pintype "bidirectional"))
    )
    (net (code "82") (name "unconnected-(IC7-VREF-Pad4)") (class "Default")
      (node (ref "IC7") (pin "4") (pinfunction "VREF_4") (pintype "bidirectional"))
    )
    (net (code "83") (name "unconnected-(IC8-VREF-Pad4)") (class "Default")
      (node (ref "IC8") (pin "4") (pinfunction "VREF_4") (pintype "bidirectional"))
    )
    (net (code "84") (name "unconnected-(RJ1-Pad4)") (class "Default")
      (node (ref "RJ1") (pin "4") (pinfunction "4_4") (pintype "bidirectional"))
    )
    (net (code "85") (name "unconnected-(RJ1-Pad5)") (class "Default")
      (node (ref "RJ1") (pin "5") (pinfunction "5_5") (pintype "bidirectional"))
    )
    (net (code "86") (name "unconnected-(RJ1-Pad7)") (class "Default")
      (node (ref "RJ1") (pin "7") (pinfunction "7_7") (pintype "bidirectional"))
    )
    (net (code "87") (name "unconnected-(RJ1-Pad8)") (class "Default")
      (node (ref "RJ1") (pin "8") (pinfunction "8_8") (pintype "bidirectional"))
    )
  )
)
